# as14120_usb.net
KiCad netlist of a schematic drawn in Altium Designer
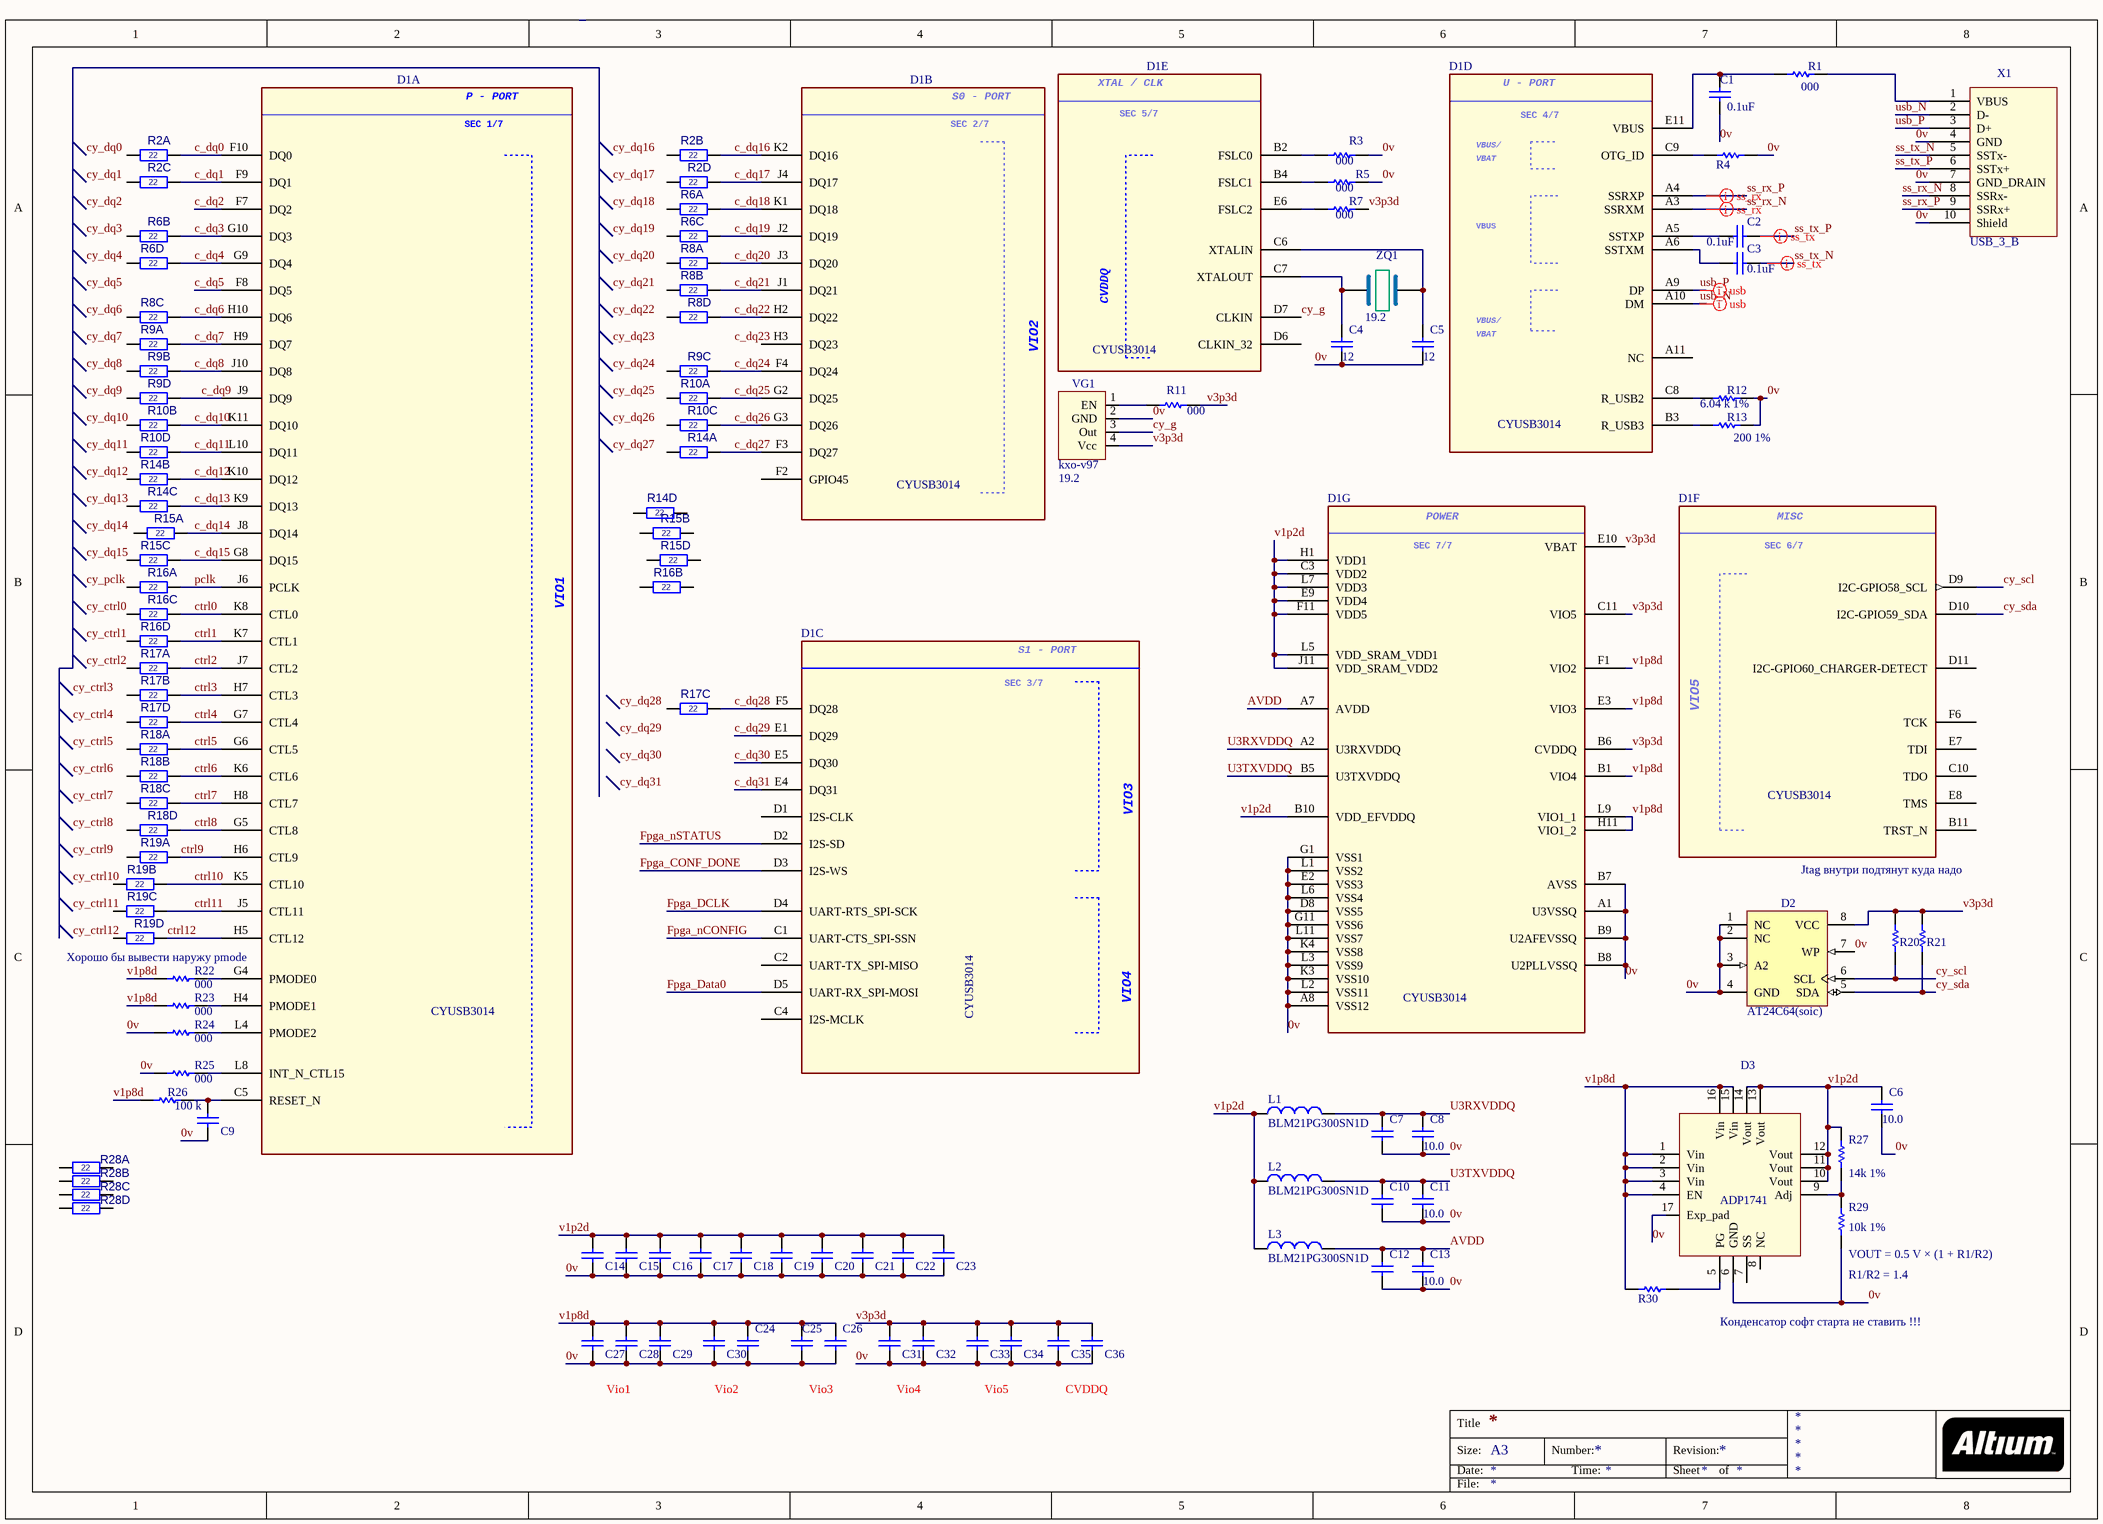
[diagram p0: as14120_usb.SchDoc]

(export (version "E")
  (design (tool "Eeschema 10.0.6"))
  (components
    (comp (ref "C1")
      (value "0.1uF")
      (footprint "CAPC0402(1005)60_M")
      (description "CAP 1uF 10V ±20% 0402 (1005 Metric) Thickness 0.6mm SMD")
      (fields (field (name "TOLERANCE") "±20%") (field (name "Comment") "CAP 1uF 10V 0402(1005)"))
      (libsource (lib "as14120") (part "CAP_0402"))
    )
    (comp (ref "C2")
      (value "0.1uF")
      (footprint "CAPC0402(1005)60_M")
      (description "CAP 1uF 10V ±20% 0402 (1005 Metric) Thickness 0.6mm SMD")
      (fields (field (name "TOLERANCE") "±20%") (field (name "Comment") "CAP 1uF 10V 0402(1005)"))
      (libsource (lib "as14120") (part "CAP_0402"))
    )
    (comp (ref "C3")
      (value "0.1uF")
      (footprint "CAPC0402(1005)60_M")
      (description "CAP 1uF 10V ±20% 0402 (1005 Metric) Thickness 0.6mm SMD")
      (fields (field (name "TOLERANCE") "±20%") (field (name "Comment") "CAP 1uF 10V 0402(1005)"))
      (libsource (lib "as14120") (part "CAP_0402"))
    )
    (comp (ref "C4")
      (value "12")
      (footprint "CAPC0805(2012)100_N")
      (fields (field (name "Comment") "CAP_0805"))
      (libsource (lib "as14120") (part "CAP_0805"))
    )
    (comp (ref "C5")
      (value "12")
      (footprint "CAPC0805(2012)100_N")
      (fields (field (name "Comment") "CAP_0805"))
      (libsource (lib "as14120") (part "CAP_0805"))
    )
    (comp (ref "C6")
      (value "10.0")
      (footprint "CAPC0805(2012)100_N")
      (fields (field (name "Comment") "CAP_0805"))
      (libsource (lib "as14120") (part "CAP_0805"))
    )
    (comp (ref "C7")
      (value "CAP 1uF 10V 0402(1005)")
      (footprint "CAPC0402(1005)60_M")
      (description "CAP 1uF 10V ±20% 0402 (1005 Metric) Thickness 0.6mm SMD")
      (fields (field (name "TOLERANCE") "±20%"))
      (libsource (lib "as14120") (part "CAP_0402"))
    )
    (comp (ref "C8")
      (value "10.0")
      (footprint "CAPC0805(2012)100_N")
      (fields (field (name "Comment") "CAP_0805"))
      (libsource (lib "as14120") (part "CAP_0805"))
    )
    (comp (ref "C9")
      (value "CAP 1uF 10V 0402(1005)")
      (footprint "CAPC0402(1005)60_M")
      (description "CAP 1uF 10V ±20% 0402 (1005 Metric) Thickness 0.6mm SMD")
      (fields (field (name "TOLERANCE") "±20%"))
      (libsource (lib "as14120") (part "CAP_0402"))
    )
    (comp (ref "C10")
      (value "CAP 1uF 10V 0402(1005)")
      (footprint "CAPC0402(1005)60_M")
      (description "CAP 1uF 10V ±20% 0402 (1005 Metric) Thickness 0.6mm SMD")
      (fields (field (name "TOLERANCE") "±20%"))
      (libsource (lib "as14120") (part "CAP_0402"))
    )
    (comp (ref "C11")
      (value "10.0")
      (footprint "CAPC0805(2012)100_N")
      (fields (field (name "Comment") "CAP_0805"))
      (libsource (lib "as14120") (part "CAP_0805"))
    )
    (comp (ref "C12")
      (value "CAP 1uF 10V 0402(1005)")
      (footprint "CAPC0402(1005)60_M")
      (description "CAP 1uF 10V ±20% 0402 (1005 Metric) Thickness 0.6mm SMD")
      (fields (field (name "TOLERANCE") "±20%"))
      (libsource (lib "as14120") (part "CAP_0402"))
    )
    (comp (ref "C13")
      (value "10.0")
      (footprint "CAPC0805(2012)100_N")
      (fields (field (name "Comment") "CAP_0805"))
      (libsource (lib "as14120") (part "CAP_0805"))
    )
    (comp (ref "C14")
      (value "CAP 1uF 10V 0402(1005)")
      (footprint "CAPC0402(1005)60_M")
      (description "CAP 1uF 10V ±20% 0402 (1005 Metric) Thickness 0.6mm SMD")
      (fields (field (name "TOLERANCE") "±20%"))
      (libsource (lib "as14120") (part "CAP_0402"))
    )
    (comp (ref "C15")
      (value "CAP 1uF 10V 0402(1005)")
      (footprint "CAPC0402(1005)60_M")
      (description "CAP 1uF 10V ±20% 0402 (1005 Metric) Thickness 0.6mm SMD")
      (fields (field (name "TOLERANCE") "±20%"))
      (libsource (lib "as14120") (part "CAP_0402"))
    )
    (comp (ref "C16")
      (value "CAP 1uF 10V 0402(1005)")
      (footprint "CAPC0402(1005)60_M")
      (description "CAP 1uF 10V ±20% 0402 (1005 Metric) Thickness 0.6mm SMD")
      (fields (field (name "TOLERANCE") "±20%"))
      (libsource (lib "as14120") (part "CAP_0402"))
    )
    (comp (ref "C17")
      (value "CAP 1uF 10V 0402(1005)")
      (footprint "CAPC0402(1005)60_M")
      (description "CAP 1uF 10V ±20% 0402 (1005 Metric) Thickness 0.6mm SMD")
      (fields (field (name "TOLERANCE") "±20%"))
      (libsource (lib "as14120") (part "CAP_0402"))
    )
    (comp (ref "C18")
      (value "CAP 1uF 10V 0402(1005)")
      (footprint "CAPC0402(1005)60_M")
      (description "CAP 1uF 10V ±20% 0402 (1005 Metric) Thickness 0.6mm SMD")
      (fields (field (name "TOLERANCE") "±20%"))
      (libsource (lib "as14120") (part "CAP_0402"))
    )
    (comp (ref "C19")
      (value "CAP 1uF 10V 0402(1005)")
      (footprint "CAPC0402(1005)60_M")
      (description "CAP 1uF 10V ±20% 0402 (1005 Metric) Thickness 0.6mm SMD")
      (fields (field (name "TOLERANCE") "±20%"))
      (libsource (lib "as14120") (part "CAP_0402"))
    )
    (comp (ref "C20")
      (value "CAP 1uF 10V 0402(1005)")
      (footprint "CAPC0402(1005)60_M")
      (description "CAP 1uF 10V ±20% 0402 (1005 Metric) Thickness 0.6mm SMD")
      (fields (field (name "TOLERANCE") "±20%"))
      (libsource (lib "as14120") (part "CAP_0402"))
    )
    (comp (ref "C21")
      (value "CAP 1uF 10V 0402(1005)")
      (footprint "CAPC0402(1005)60_M")
      (description "CAP 1uF 10V ±20% 0402 (1005 Metric) Thickness 0.6mm SMD")
      (fields (field (name "TOLERANCE") "±20%"))
      (libsource (lib "as14120") (part "CAP_0402"))
    )
    (comp (ref "C22")
      (value "CAP 1uF 10V 0402(1005)")
      (footprint "CAPC0402(1005)60_M")
      (description "CAP 1uF 10V ±20% 0402 (1005 Metric) Thickness 0.6mm SMD")
      (fields (field (name "TOLERANCE") "±20%"))
      (libsource (lib "as14120") (part "CAP_0402"))
    )
    (comp (ref "C23")
      (value "CAP 1uF 10V 0402(1005)")
      (footprint "CAPC0402(1005)60_M")
      (description "CAP 1uF 10V ±20% 0402 (1005 Metric) Thickness 0.6mm SMD")
      (fields (field (name "TOLERANCE") "±20%"))
      (libsource (lib "as14120") (part "CAP_0402"))
    )
    (comp (ref "C24")
      (value "CAP 1uF 10V 0402(1005)")
      (footprint "CAPC0402(1005)60_M")
      (description "CAP 1uF 10V ±20% 0402 (1005 Metric) Thickness 0.6mm SMD")
      (fields (field (name "TOLERANCE") "±20%"))
      (libsource (lib "as14120") (part "CAP_0402"))
    )
    (comp (ref "C25")
      (value "CAP 1uF 10V 0402(1005)")
      (footprint "CAPC0402(1005)60_M")
      (description "CAP 1uF 10V ±20% 0402 (1005 Metric) Thickness 0.6mm SMD")
      (fields (field (name "TOLERANCE") "±20%"))
      (libsource (lib "as14120") (part "CAP_0402"))
    )
    (comp (ref "C26")
      (value "CAP 1uF 10V 0402(1005)")
      (footprint "CAPC0402(1005)60_M")
      (description "CAP 1uF 10V ±20% 0402 (1005 Metric) Thickness 0.6mm SMD")
      (fields (field (name "TOLERANCE") "±20%"))
      (libsource (lib "as14120") (part "CAP_0402"))
    )
    (comp (ref "C27")
      (value "CAP 1uF 10V 0402(1005)")
      (footprint "CAPC0402(1005)60_M")
      (description "CAP 1uF 10V ±20% 0402 (1005 Metric) Thickness 0.6mm SMD")
      (fields (field (name "TOLERANCE") "±20%"))
      (libsource (lib "as14120") (part "CAP_0402"))
    )
    (comp (ref "C28")
      (value "CAP 1uF 10V 0402(1005)")
      (footprint "CAPC0402(1005)60_M")
      (description "CAP 1uF 10V ±20% 0402 (1005 Metric) Thickness 0.6mm SMD")
      (fields (field (name "TOLERANCE") "±20%"))
      (libsource (lib "as14120") (part "CAP_0402"))
    )
    (comp (ref "C29")
      (value "CAP 1uF 10V 0402(1005)")
      (footprint "CAPC0402(1005)60_M")
      (description "CAP 1uF 10V ±20% 0402 (1005 Metric) Thickness 0.6mm SMD")
      (fields (field (name "TOLERANCE") "±20%"))
      (libsource (lib "as14120") (part "CAP_0402"))
    )
    (comp (ref "C30")
      (value "CAP 1uF 10V 0402(1005)")
      (footprint "CAPC0402(1005)60_M")
      (description "CAP 1uF 10V ±20% 0402 (1005 Metric) Thickness 0.6mm SMD")
      (fields (field (name "TOLERANCE") "±20%"))
      (libsource (lib "as14120") (part "CAP_0402"))
    )
    (comp (ref "C31")
      (value "CAP 1uF 10V 0402(1005)")
      (footprint "CAPC0402(1005)60_M")
      (description "CAP 1uF 10V ±20% 0402 (1005 Metric) Thickness 0.6mm SMD")
      (fields (field (name "TOLERANCE") "±20%"))
      (libsource (lib "as14120") (part "CAP_0402"))
    )
    (comp (ref "C32")
      (value "CAP 1uF 10V 0402(1005)")
      (footprint "CAPC0402(1005)60_M")
      (description "CAP 1uF 10V ±20% 0402 (1005 Metric) Thickness 0.6mm SMD")
      (fields (field (name "TOLERANCE") "±20%"))
      (libsource (lib "as14120") (part "CAP_0402"))
    )
    (comp (ref "C33")
      (value "CAP 1uF 10V 0402(1005)")
      (footprint "CAPC0402(1005)60_M")
      (description "CAP 1uF 10V ±20% 0402 (1005 Metric) Thickness 0.6mm SMD")
      (fields (field (name "TOLERANCE") "±20%"))
      (libsource (lib "as14120") (part "CAP_0402"))
    )
    (comp (ref "C34")
      (value "CAP 1uF 10V 0402(1005)")
      (footprint "CAPC0402(1005)60_M")
      (description "CAP 1uF 10V ±20% 0402 (1005 Metric) Thickness 0.6mm SMD")
      (fields (field (name "TOLERANCE") "±20%"))
      (libsource (lib "as14120") (part "CAP_0402"))
    )
    (comp (ref "C35")
      (value "CAP 1uF 10V 0402(1005)")
      (footprint "CAPC0402(1005)60_M")
      (description "CAP 1uF 10V ±20% 0402 (1005 Metric) Thickness 0.6mm SMD")
      (fields (field (name "TOLERANCE") "±20%"))
      (libsource (lib "as14120") (part "CAP_0402"))
    )
    (comp (ref "C36")
      (value "CAP 1uF 10V 0402(1005)")
      (footprint "CAPC0402(1005)60_M")
      (description "CAP 1uF 10V ±20% 0402 (1005 Metric) Thickness 0.6mm SMD")
      (fields (field (name "TOLERANCE") "±20%"))
      (libsource (lib "as14120") (part "CAP_0402"))
    )
    (comp (ref "D1")
      (value "CYUSB3014")
      (footprint "BGA121C80P11X11")
      (libsource (lib "as14120") (part "CYUSB3014-BZXC"))
    )
    (comp (ref "D2")
      (value "AT24C64(soic)")
      (footprint "8S1_N")
      (libsource (lib "Atmel Serial EEPROM") (part "AT24C08BN-SP25-T"))
    )
    (comp (ref "D3") (value "ADP1741") (footprint "CP-16-4_N") (libsource (lib "as14120") (part "ADP1741")))
    (comp (ref "L1")
      (value "BLM21PG300SN1D")
      (footprint "CAPC0805(2012)100_N")
      (libsource (lib "as14120") (part "Ferrite_beat"))
    )
    (comp (ref "L2")
      (value "BLM21PG300SN1D")
      (footprint "CAPC0805(2012)100_N")
      (libsource (lib "as14120") (part "Ferrite_beat"))
    )
    (comp (ref "L3")
      (value "BLM21PG300SN1D")
      (footprint "CAPC0805(2012)100_N")
      (libsource (lib "as14120") (part "Ferrite_beat"))
    )
    (comp (ref "R1")
      (value "000")
      (footprint "RESC0805(2012)_L")
      (description "1K 0.125W 1% 0805 (2012 Metric)  SMD")
      (fields (field (name "TOLERANCE") "1 %") (field (name "POWER") "0.125 W"))
      (libsource (lib "as14120") (part "RES_0805"))
    )
    (comp (ref "R2")
      (value "22")
      (footprint "CAY16")
      (description "RES_CAY16")
      (libsource (lib "") (part "RES_CAY16_1"))
    )
    (comp (ref "R3")
      (value "000")
      (footprint "RESC0603(1608)_L")
      (description "1K 0.1W 5% 0603 (1608 Metric)  SMD")
      (fields (field (name "TOLERANCE") "5 %") (field (name "POWER") "0.1 W"))
      (libsource (lib "as14120") (part "RES_0603"))
    )
    (comp (ref "R4")
      (value "???")
      (footprint "RESC0603(1608)_L")
      (description "1K 0.1W 5% 0603 (1608 Metric)  SMD")
      (fields (field (name "TOLERANCE") "5 %") (field (name "POWER") "0.1 W"))
      (libsource (lib "as14120") (part "RES_0603"))
    )
    (comp (ref "R5")
      (value "000")
      (footprint "RESC0603(1608)_L")
      (description "1K 0.1W 5% 0603 (1608 Metric)  SMD")
      (fields (field (name "TOLERANCE") "5 %") (field (name "POWER") "0.1 W"))
      (libsource (lib "as14120") (part "RES_0603"))
    )
    (comp (ref "R6")
      (value "22")
      (footprint "CAY16")
      (description "RES_CAY16")
      (libsource (lib "") (part "RES_CAY16_7"))
    )
    (comp (ref "R7")
      (value "000")
      (footprint "RESC0603(1608)_L")
      (description "1K 0.1W 5% 0603 (1608 Metric)  SMD")
      (fields (field (name "TOLERANCE") "5 %") (field (name "POWER") "0.1 W"))
      (libsource (lib "as14120") (part "RES_0603"))
    )
    (comp (ref "R8")
      (value "22")
      (footprint "CAY16")
      (description "RES_CAY16")
      (libsource (lib "") (part "RES_CAY16_3"))
    )
    (comp (ref "R9")
      (value "22")
      (footprint "CAY16")
      (description "RES_CAY16")
      (libsource (lib "") (part "RES_CAY16_7"))
    )
    (comp (ref "R10")
      (value "22")
      (footprint "CAY16")
      (description "RES_CAY16")
      (libsource (lib "") (part "RES_CAY16_7"))
    )
    (comp (ref "R11")
      (value "000")
      (footprint "RESC0603(1608)_L")
      (description "1K 0.1W 5% 0603 (1608 Metric)  SMD")
      (fields (field (name "TOLERANCE") "5 %") (field (name "POWER") "0.1 W"))
      (libsource (lib "as14120") (part "RES_0603"))
    )
    (comp (ref "R12")
      (value "6.04 k 1%")
      (footprint "RESC0805(2012)_L")
      (description "1K 0.125W 1% 0805 (2012 Metric)  SMD")
      (fields (field (name "TOLERANCE") "1 %") (field (name "POWER") "0.125 W"))
      (libsource (lib "as14120") (part "RES_0805"))
    )
    (comp (ref "R13")
      (value "200 1%")
      (footprint "RESC0805(2012)_L")
      (description "1K 0.125W 1% 0805 (2012 Metric)  SMD")
      (fields (field (name "TOLERANCE") "1 %") (field (name "POWER") "0.125 W"))
      (libsource (lib "as14120") (part "RES_0805"))
    )
    (comp (ref "R14")
      (value "22")
      (footprint "CAY16")
      (description "RES_CAY16")
      (libsource (lib "alexsb") (part "RES_CAY16"))
    )
    (comp (ref "R15")
      (value "22")
      (footprint "CAY16")
      (description "RES_CAY16")
      (libsource (lib "") (part "RES_CAY16_3"))
    )
    (comp (ref "R16")
      (value "22")
      (footprint "CAY16")
      (description "RES_CAY16")
      (libsource (lib "alexsb") (part "RES_CAY16"))
    )
    (comp (ref "R17")
      (value "22")
      (footprint "CAY16")
      (description "RES_CAY16")
      (libsource (lib "") (part "RES_CAY16_4"))
    )
    (comp (ref "R18")
      (value "22")
      (footprint "CAY16")
      (description "RES_CAY16")
      (libsource (lib "") (part "RES_CAY16_2"))
    )
    (comp (ref "R19")
      (value "22")
      (footprint "CAY16")
      (description "RES_CAY16")
      (libsource (lib "") (part "RES_CAY16_2"))
    )
    (comp (ref "R20")
      (value "1K 5% 0603(1608)")
      (footprint "RESC0603(1608)_L")
      (description "1K 0.1W 5% 0603 (1608 Metric)  SMD")
      (fields (field (name "TOLERANCE") "5 %") (field (name "POWER") "0.1 W"))
      (libsource (lib "as14120") (part "RES_0603"))
    )
    (comp (ref "R21")
      (value "1K 5% 0603(1608)")
      (footprint "RESC0603(1608)_L")
      (description "1K 0.1W 5% 0603 (1608 Metric)  SMD")
      (fields (field (name "TOLERANCE") "5 %") (field (name "POWER") "0.1 W"))
      (libsource (lib "as14120") (part "RES_0603"))
    )
    (comp (ref "R22")
      (value "000")
      (footprint "RESC0603(1608)_L")
      (description "1K 0.1W 5% 0603 (1608 Metric)  SMD")
      (fields (field (name "TOLERANCE") "5 %") (field (name "POWER") "0.1 W"))
      (libsource (lib "as14120") (part "RES_0603"))
    )
    (comp (ref "R23")
      (value "000")
      (footprint "RESC0603(1608)_L")
      (description "1K 0.1W 5% 0603 (1608 Metric)  SMD")
      (fields (field (name "TOLERANCE") "5 %") (field (name "POWER") "0.1 W"))
      (libsource (lib "as14120") (part "RES_0603"))
    )
    (comp (ref "R24")
      (value "000")
      (footprint "RESC0603(1608)_L")
      (description "1K 0.1W 5% 0603 (1608 Metric)  SMD")
      (fields (field (name "TOLERANCE") "5 %") (field (name "POWER") "0.1 W"))
      (libsource (lib "as14120") (part "RES_0603"))
    )
    (comp (ref "R25")
      (value "000")
      (footprint "RESC0603(1608)_L")
      (description "1K 0.1W 5% 0603 (1608 Metric)  SMD")
      (fields (field (name "TOLERANCE") "5 %") (field (name "POWER") "0.1 W"))
      (libsource (lib "as14120") (part "RES_0603"))
    )
    (comp (ref "R26")
      (value "100 k")
      (footprint "RESC0603(1608)_L")
      (description "1K 0.1W 5% 0603 (1608 Metric)  SMD")
      (fields (field (name "TOLERANCE") "5 %") (field (name "POWER") "0.1 W"))
      (libsource (lib "as14120") (part "RES_0603"))
    )
    (comp (ref "R27")
      (value "14k 1%")
      (footprint "RESC0805(2012)_L")
      (description "1K 0.125W 1% 0805 (2012 Metric)  SMD")
      (fields (field (name "TOLERANCE") "1 %") (field (name "POWER") "0.125 W"))
      (libsource (lib "as14120") (part "RES_0805"))
    )
    (comp (ref "R28")
      (value "22")
      (footprint "CAY16")
      (description "RES_CAY16")
      (libsource (lib "alexsb") (part "RES_CAY16"))
    )
    (comp (ref "R29")
      (value "10k 1%")
      (footprint "RESC0805(2012)_L")
      (description "1K 0.125W 1% 0805 (2012 Metric)  SMD")
      (fields (field (name "TOLERANCE") "1 %") (field (name "POWER") "0.125 W"))
      (libsource (lib "as14120") (part "RES_0805"))
    )
    (comp (ref "R30")
      (value "1K 5% 0603(1608)")
      (footprint "RESC0603(1608)_L")
      (description "1K 0.1W 5% 0603 (1608 Metric)  SMD")
      (fields (field (name "TOLERANCE") "5 %") (field (name "POWER") "0.1 W"))
      (libsource (lib "as14120") (part "RES_0603"))
    )
    (comp (ref "VG1")
      (value "kxo-v97")
      (footprint "kxo-v97")
      (fields (field (name "ALTIUM_VALUE") "19.2"))
      (libsource (lib "as14120") (part "kxo-v97"))
    )
    (comp (ref "X1") (value "USB_3_B") (footprint "USB3_B") (libsource (lib "as14120") (part "USB_3_B")))
    (comp (ref "ZQ1")
      (value "19.2")
      (footprint "BCY-W2/E4.7")
      (fields (field (name "Comment") "Resonator"))
      (libsource (lib "as14120") (part "Resonator"))
    )
  )
  (nets
    (net (code "1") (name "/0v") (class "Default")
      (node (ref "C1") (pin "2") (pinfunction "2_2") (pintype "passive"))
      (node (ref "C10") (pin "1") (pinfunction "1_1") (pintype "passive"))
      (node (ref "C11") (pin "1") (pinfunction "1_1") (pintype "passive"))
      (node (ref "C12") (pin "1") (pinfunction "1_1") (pintype "passive"))
      (node (ref "C13") (pin "1") (pinfunction "1_1") (pintype "passive"))
      (node (ref "C14") (pin "1") (pinfunction "1_1") (pintype "passive"))
      (node (ref "C15") (pin "1") (pinfunction "1_1") (pintype "passive"))
      (node (ref "C16") (pin "1") (pinfunction "1_1") (pintype "passive"))
      (node (ref "C17") (pin "1") (pinfunction "1_1") (pintype "passive"))
      (node (ref "C18") (pin "1") (pinfunction "1_1") (pintype "passive"))
      (node (ref "C19") (pin "1") (pinfunction "1_1") (pintype "passive"))
      (node (ref "C20") (pin "1") (pinfunction "1_1") (pintype "passive"))
      (node (ref "C21") (pin "1") (pinfunction "1_1") (pintype "passive"))
      (node (ref "C22") (pin "1") (pinfunction "1_1") (pintype "passive"))
      (node (ref "C23") (pin "1") (pinfunction "1_1") (pintype "passive"))
      (node (ref "C24") (pin "1") (pinfunction "1_1") (pintype "passive"))
      (node (ref "C25") (pin "1") (pinfunction "1_1") (pintype "passive"))
      (node (ref "C26") (pin "1") (pinfunction "1_1") (pintype "passive"))
      (node (ref "C27") (pin "1") (pinfunction "1_1") (pintype "passive"))
      (node (ref "C28") (pin "1") (pinfunction "1_1") (pintype "passive"))
      (node (ref "C29") (pin "1") (pinfunction "1_1") (pintype "passive"))
      (node (ref "C30") (pin "1") (pinfunction "1_1") (pintype "passive"))
      (node (ref "C31") (pin "1") (pinfunction "1_1") (pintype "passive"))
      (node (ref "C32") (pin "1") (pinfunction "1_1") (pintype "passive"))
      (node (ref "C33") (pin "1") (pinfunction "1_1") (pintype "passive"))
      (node (ref "C34") (pin "1") (pinfunction "1_1") (pintype "passive"))
      (node (ref "C35") (pin "1") (pinfunction "1_1") (pintype "passive"))
      (node (ref "C36") (pin "1") (pinfunction "1_1") (pintype "passive"))
      (node (ref "C4") (pin "1") (pinfunction "1_1") (pintype "passive"))
      (node (ref "C5") (pin "1") (pinfunction "1_1") (pintype "passive"))
      (node (ref "C6") (pin "1") (pinfunction "1_1") (pintype "passive"))
      (node (ref "C7") (pin "1") (pinfunction "1_1") (pintype "passive"))
      (node (ref "C8") (pin "1") (pinfunction "1_1") (pintype "passive"))
      (node (ref "C9") (pin "1") (pinfunction "1_1") (pintype "passive"))
      (node (ref "D1") (pin "A1") (pinfunction "U3VSSQ_A1") (pintype "passive"))
      (node (ref "D1") (pin "A8") (pinfunction "VSS12_A8") (pintype "passive"))
      (node (ref "D1") (pin "B7") (pinfunction "AVSS_B7") (pintype "passive"))
      (node (ref "D1") (pin "B8") (pinfunction "U2PLLVSSQ_B8") (pintype "passive"))
      (node (ref "D1") (pin "B9") (pinfunction "U2AFEVSSQ_B9") (pintype "passive"))
      (node (ref "D1") (pin "D8") (pinfunction "VSS5_D8") (pintype "passive"))
      (node (ref "D1") (pin "E2") (pinfunction "VSS3_E2") (pintype "passive"))
      (node (ref "D1") (pin "G1") (pinfunction "VSS1_G1") (pintype "passive"))
      (node (ref "D1") (pin "G11") (pinfunction "VSS6_G11") (pintype "passive"))
      (node (ref "D1") (pin "K3") (pinfunction "VSS10_K3") (pintype "passive"))
      (node (ref "D1") (pin "K4") (pinfunction "VSS8_K4") (pintype "passive"))
      (node (ref "D1") (pin "L1") (pinfunction "VSS2_L1") (pintype "passive"))
      (node (ref "D1") (pin "L11") (pinfunction "VSS7_L11") (pintype "passive"))
      (node (ref "D1") (pin "L2") (pinfunction "VSS11_L2") (pintype "passive"))
      (node (ref "D1") (pin "L3") (pinfunction "VSS9_L3") (pintype "passive"))
      (node (ref "D1") (pin "L6") (pinfunction "VSS4_L6") (pintype "passive"))
      (node (ref "D2") (pin "1") (pinfunction "NC_1") (pintype "passive"))
      (node (ref "D2") (pin "2") (pinfunction "NC_2") (pintype "passive"))
      (node (ref "D2") (pin "3") (pinfunction "A2_3") (pintype "input"))
      (node (ref "D2") (pin "4") (pinfunction "GND_4") (pintype "power_in"))
      (node (ref "D2") (pin "7") (pinfunction "WP_7") (pintype "input"))
      (node (ref "D3") (pin "17") (pinfunction "Exp_pad_17") (pintype "passive"))
      (node (ref "D3") (pin "6") (pinfunction "GND_6") (pintype "passive"))
      (node (ref "R12") (pin "2") (pinfunction "2_2") (pintype "passive"))
      (node (ref "R13") (pin "2") (pinfunction "2_2") (pintype "passive"))
      (node (ref "R24") (pin "2") (pinfunction "2_2") (pintype "passive"))
      (node (ref "R25") (pin "2") (pinfunction "2_2") (pintype "passive"))
      (node (ref "R29") (pin "1") (pinfunction "1_1") (pintype "passive"))
      (node (ref "R3") (pin "1") (pinfunction "1_1") (pintype "passive"))
      (node (ref "R4") (pin "2") (pinfunction "2_2") (pintype "passive"))
      (node (ref "R5") (pin "1") (pinfunction "1_1") (pintype "passive"))
      (node (ref "VG1") (pin "2") (pinfunction "GND_2") (pintype "passive"))
      (node (ref "X1") (pin "10") (pinfunction "Shield_10") (pintype "passive"))
      (node (ref "X1") (pin "4") (pinfunction "GND_4") (pintype "passive"))
      (node (ref "X1") (pin "7") (pinfunction "GND_DRAIN_7") (pintype "passive"))
    )
    (net (code "2") (name "/AVDD") (class "Default")
      (node (ref "C12") (pin "2") (pinfunction "2_2") (pintype "passive"))
      (node (ref "C13") (pin "2") (pinfunction "2_2") (pintype "passive"))
      (node (ref "D1") (pin "A7") (pinfunction "AVDD_A7") (pintype "passive"))
      (node (ref "L3") (pin "2") (pinfunction "2_2") (pintype "passive"))
    )
    (net (code "3") (name "/Fpga_CONF_DONE") (class "Default")
      (node (ref "D1") (pin "D3") (pinfunction "I2S-WS_D3") (pintype "passive"))
    )
    (net (code "4") (name "/Fpga_DCLK") (class "Default")
      (node (ref "D1") (pin "D4") (pinfunction "UART-RTS_SPI-SCK_D4") (pintype "passive"))
    )
    (net (code "5") (name "/Fpga_Data0") (class "Default")
      (node (ref "D1") (pin "D5") (pinfunction "UART-RX_SPI-MOSI_D5") (pintype "passive"))
    )
    (net (code "6") (name "/Fpga_nCONFIG") (class "Default")
      (node (ref "D1") (pin "C1") (pinfunction "UART-CTS_SPI-SSN_C1") (pintype "passive"))
    )
    (net (code "7") (name "/Fpga_nSTATUS") (class "Default")
      (node (ref "D1") (pin "D2") (pinfunction "I2S-SD_D2") (pintype "passive"))
    )
    (net (code "8") (name "/U3RXVDDQ") (class "Default")
      (node (ref "C7") (pin "2") (pinfunction "2_2") (pintype "passive"))
      (node (ref "C8") (pin "2") (pinfunction "2_2") (pintype "passive"))
      (node (ref "D1") (pin "A2") (pinfunction "U3RXVDDQ_A2") (pintype "passive"))
      (node (ref "L1") (pin "2") (pinfunction "2_2") (pintype "passive"))
    )
    (net (code "9") (name "/U3TXVDDQ") (class "Default")
      (node (ref "C10") (pin "2") (pinfunction "2_2") (pintype "passive"))
      (node (ref "C11") (pin "2") (pinfunction "2_2") (pintype "passive"))
      (node (ref "D1") (pin "B5") (pinfunction "U3TXVDDQ_B5") (pintype "passive"))
      (node (ref "L2") (pin "2") (pinfunction "2_2") (pintype "passive"))
    )
    (net (code "10") (name "/c_dq0") (class "Default")
      (node (ref "D1") (pin "F10") (pinfunction "DQ0_F10") (pintype "passive"))
      (node (ref "R2") (pin "8") (pinfunction "2_8") (pintype "passive"))
    )
    (net (code "11") (name "/c_dq1") (class "Default")
      (node (ref "D1") (pin "F9") (pinfunction "DQ1_F9") (pintype "passive"))
      (node (ref "R2") (pin "6") (pinfunction "2_6") (pintype "passive"))
    )
    (net (code "12") (name "/c_dq2") (class "Default")
      (node (ref "D1") (pin "F7") (pinfunction "DQ2_F7") (pintype "passive"))
    )
    (net (code "13") (name "/c_dq3") (class "Default")
      (node (ref "D1") (pin "G10") (pinfunction "DQ3_G10") (pintype "passive"))
      (node (ref "R6") (pin "7") (pinfunction "2_7") (pintype "passive"))
    )
    (net (code "14") (name "/c_dq4") (class "Default")
      (node (ref "D1") (pin "G9") (pinfunction "DQ4_G9") (pintype "passive"))
      (node (ref "R6") (pin "8") (pinfunction "2_8") (pintype "passive"))
    )
    (net (code "15") (name "/c_dq5") (class "Default")
      (node (ref "D1") (pin "F8") (pinfunction "DQ5_F8") (pintype "passive"))
    )
    (net (code "16") (name "/c_dq6") (class "Default")
      (node (ref "D1") (pin "H10") (pinfunction "DQ6_H10") (pintype "passive"))
      (node (ref "R8") (pin "6") (pinfunction "2_6") (pintype "passive"))
    )
    (net (code "17") (name "/c_dq7") (class "Default")
      (node (ref "D1") (pin "H9") (pinfunction "DQ7_H9") (pintype "passive"))
      (node (ref "R9") (pin "8") (pinfunction "2_8") (pintype "passive"))
    )
    (net (code "18") (name "/c_dq8") (class "Default")
      (node (ref "D1") (pin "J10") (pinfunction "DQ8_J10") (pintype "passive"))
      (node (ref "R9") (pin "7") (pinfunction "2_7") (pintype "passive"))
    )
    (net (code "19") (name "/c_dq9") (class "Default")
      (node (ref "D1") (pin "J9") (pinfunction "DQ9_J9") (pintype "passive"))
      (node (ref "R9") (pin "8") (pinfunction "2_8") (pintype "passive"))
    )
    (net (code "20") (name "/c_dq10") (class "Default")
      (node (ref "D1") (pin "K11") (pinfunction "DQ10_K11") (pintype "passive"))
      (node (ref "R10") (pin "7") (pinfunction "2_7") (pintype "passive"))
    )
    (net (code "21") (name "/c_dq11") (class "Default")
      (node (ref "D1") (pin "L10") (pinfunction "DQ11_L10") (pintype "passive"))
      (node (ref "R10") (pin "8") (pinfunction "2_8") (pintype "passive"))
    )
    (net (code "22") (name "/c_dq12") (class "Default")
      (node (ref "D1") (pin "K10") (pinfunction "DQ12_K10") (pintype "passive"))
      (node (ref "R14") (pin "7") (pinfunction "2_7") (pintype "passive"))
    )
    (net (code "23") (name "/c_dq13") (class "Default")
      (node (ref "D1") (pin "K9") (pinfunction "DQ13_K9") (pintype "passive"))
      (node (ref "R14") (pin "6") (pinfunction "2_6") (pintype "passive"))
    )
    (net (code "24") (name "/c_dq14") (class "Default")
      (node (ref "D1") (pin "J8") (pinfunction "DQ14_J8") (pintype "passive"))
      (node (ref "R15") (pin "8") (pinfunction "2_8") (pintype "passive"))
    )
    (net (code "25") (name "/c_dq15") (class "Default")
      (node (ref "D1") (pin "G8") (pinfunction "DQ15_G8") (pintype "passive"))
      (node (ref "R15") (pin "7") (pinfunction "2_7") (pintype "passive"))
    )
    (net (code "26") (name "/c_dq16") (class "Default")
      (node (ref "D1") (pin "K2") (pinfunction "DQ16_K2") (pintype "passive"))
      (node (ref "R2") (pin "7") (pinfunction "2_7") (pintype "passive"))
    )
    (net (code "27") (name "/c_dq17") (class "Default")
      (node (ref "D1") (pin "J4") (pinfunction "DQ17_J4") (pintype "passive"))
      (node (ref "R2") (pin "5") (pinfunction "2_5") (pintype "passive"))
    )
    (net (code "28") (name "/c_dq18") (class "Default")
      (node (ref "D1") (pin "K1") (pinfunction "DQ18_K1") (pintype "passive"))
      (node (ref "R6") (pin "8") (pinfunction "2_8") (pintype "passive"))
    )
    (net (code "29") (name "/c_dq19") (class "Default")
      (node (ref "D1") (pin "J2") (pinfunction "DQ19_J2") (pintype "passive"))
      (node (ref "R6") (pin "6") (pinfunction "2_6") (pintype "passive"))
    )
    (net (code "30") (name "/c_dq20") (class "Default")
      (node (ref "D1") (pin "J3") (pinfunction "DQ20_J3") (pintype "passive"))
      (node (ref "R8") (pin "7") (pinfunction "2_7") (pintype "passive"))
    )
    (net (code "31") (name "/c_dq21") (class "Default")
      (node (ref "D1") (pin "J1") (pinfunction "DQ21_J1") (pintype "passive"))
      (node (ref "R8") (pin "6") (pinfunction "2_6") (pintype "passive"))
    )
    (net (code "32") (name "/c_dq22") (class "Default")
      (node (ref "D1") (pin "H2") (pinfunction "DQ22_H2") (pintype "passive"))
      (node (ref "R8") (pin "5") (pinfunction "2_5") (pintype "passive"))
    )
    (net (code "34") (name "/c_dq24") (class "Default")
      (node (ref "D1") (pin "F4") (pinfunction "DQ24_F4") (pintype "passive"))
      (node (ref "R9") (pin "7") (pinfunction "2_7") (pintype "passive"))
    )
    (net (code "35") (name "/c_dq25") (class "Default")
      (node (ref "D1") (pin "G2") (pinfunction "DQ25_G2") (pintype "passive"))
      (node (ref "R10") (pin "8") (pinfunction "2_8") (pintype "passive"))
    )
    (net (code "36") (name "/c_dq26") (class "Default")
      (node (ref "D1") (pin "G3") (pinfunction "DQ26_G3") (pintype "passive"))
      (node (ref "R10") (pin "6") (pinfunction "2_6") (pintype "passive"))
    )
    (net (code "37") (name "/c_dq27") (class "Default")
      (node (ref "D1") (pin "F3") (pinfunction "DQ27_F3") (pintype "passive"))
      (node (ref "R14") (pin "8") (pinfunction "2_8") (pintype "passive"))
    )
    (net (code "38") (name "/c_dq28") (class "Default")
      (node (ref "D1") (pin "F5") (pinfunction "DQ28_F5") (pintype "passive"))
      (node (ref "R17") (pin "6") (pinfunction "2_6") (pintype "passive"))
    )
    (net (code "39") (name "/c_dq29") (class "Default")
      (node (ref "D1") (pin "E1") (pinfunction "DQ29_E1") (pintype "passive"))
    )
    (net (code "40") (name "/c_dq30") (class "Default")
      (node (ref "D1") (pin "E5") (pinfunction "DQ30_E5") (pintype "passive"))
    )
    (net (code "41") (name "/c_dq31") (class "Default")
      (node (ref "D1") (pin "E4") (pinfunction "DQ31_E4") (pintype "passive"))
    )
    (net (code "42") (name "/ctrl0") (class "Default")
      (node (ref "D1") (pin "K8") (pinfunction "CTL0_K8") (pintype "passive"))
      (node (ref "R16") (pin "6") (pinfunction "2_6") (pintype "passive"))
    )
    (net (code "43") (name "/ctrl1") (class "Default")
      (node (ref "D1") (pin "K7") (pinfunction "CTL1_K7") (pintype "passive"))
      (node (ref "R16") (pin "5") (pinfunction "2_5") (pintype "passive"))
    )
    (net (code "44") (name "/ctrl2") (class "Default")
      (node (ref "D1") (pin "J7") (pinfunction "CTL2_J7") (pintype "passive"))
      (node (ref "R17") (pin "8") (pinfunction "2_8") (pintype "passive"))
    )
    (net (code "45") (name "/ctrl3") (class "Default")
      (node (ref "D1") (pin "H7") (pinfunction "CTL3_H7") (pintype "passive"))
      (node (ref "R17") (pin "7") (pinfunction "2_7") (pintype "passive"))
    )
    (net (code "46") (name "/ctrl4") (class "Default")
      (node (ref "D1") (pin "G7") (pinfunction "CTL4_G7") (pintype "passive"))
      (node (ref "R17") (pin "5") (pinfunction "2_5") (pintype "passive"))
    )
    (net (code "47") (name "/ctrl5") (class "Default")
      (node (ref "D1") (pin "G6") (pinfunction "CTL5_G6") (pintype "passive"))
      (node (ref "R18") (pin "8") (pinfunction "2_8") (pintype "passive"))
    )
    (net (code "48") (name "/ctrl6") (class "Default")
      (node (ref "D1") (pin "K6") (pinfunction "CTL6_K6") (pintype "passive"))
      (node (ref "R18") (pin "7") (pinfunction "2_7") (pintype "passive"))
    )
    (net (code "49") (name "/ctrl7") (class "Default")
      (node (ref "D1") (pin "H8") (pinfunction "CTL7_H8") (pintype "passive"))
      (node (ref "R18") (pin "7") (pinfunction "2_7") (pintype "passive"))
    )
    (net (code "50") (name "/ctrl8") (class "Default")
      (node (ref "D1") (pin "G5") (pinfunction "CTL8_G5") (pintype "passive"))
      (node (ref "R18") (pin "5") (pinfunction "2_5") (pintype "passive"))
    )
    (net (code "51") (name "/ctrl9") (class "Default")
      (node (ref "D1") (pin "H6") (pinfunction "CTL9_H6") (pintype "passive"))
      (node (ref "R19") (pin "5") (pinfunction "2_5") (pintype "passive"))
    )
    (net (code "52") (name "/ctrl10") (class "Default")
      (node (ref "D1") (pin "K5") (pinfunction "CTL10_K5") (pintype "passive"))
      (node (ref "R19") (pin "7") (pinfunction "2_7") (pintype "passive"))
    )
    (net (code "53") (name "/ctrl11") (class "Default")
      (node (ref "D1") (pin "J5") (pinfunction "CTL11_J5") (pintype "passive"))
      (node (ref "R19") (pin "6") (pinfunction "2_6") (pintype "passive"))
    )
    (net (code "54") (name "/ctrl12") (class "Default")
      (node (ref "D1") (pin "H5") (pinfunction "CTL12_H5") (pintype "passive"))
      (node (ref "R19") (pin "5") (pinfunction "2_5") (pintype "passive"))
    )
    (net (code "100") (name "/cy_g") (class "Default")
      (node (ref "D1") (pin "D7") (pinfunction "CLKIN_D7") (pintype "passive"))
      (node (ref "VG1") (pin "3") (pinfunction "Out_3") (pintype "passive"))
    )
    (net (code "102") (name "/cy_scl") (class "Default")
      (node (ref "D1") (pin "D9") (pinfunction "I2C-GPIO58_SCL_D9") (pintype "output"))
      (node (ref "D2") (pin "6") (pinfunction "SCL_6") (pintype "input"))
      (node (ref "R20") (pin "1") (pinfunction "1_1") (pintype "passive"))
    )
    (net (code "103") (name "/cy_sda") (class "Default")
      (node (ref "D1") (pin "D10") (pinfunction "I2C-GPIO59_SDA_D10") (pintype "passive"))
      (node (ref "D2") (pin "5") (pinfunction "SDA_5") (pintype "bidirectional"))
      (node (ref "R21") (pin "1") (pinfunction "1_1") (pintype "passive"))
    )
    (net (code "104") (name "/pclk") (class "Default")
      (node (ref "D1") (pin "J6") (pinfunction "PCLK_J6") (pintype "passive"))
      (node (ref "R16") (pin "8") (pinfunction "2_8") (pintype "passive"))
    )
    (net (code "105") (name "/ss_rx_N") (class "Default")
      (node (ref "D1") (pin "A3") (pinfunction "SSRXM_A3") (pintype "passive"))
      (node (ref "X1") (pin "8") (pinfunction "SSRx-_8") (pintype "passive"))
    )
    (net (code "106") (name "/ss_rx_P") (class "Default")
      (node (ref "D1") (pin "A4") (pinfunction "SSRXP_A4") (pintype "passive"))
      (node (ref "X1") (pin "9") (pinfunction "SSRx+_9") (pintype "passive"))
    )
    (net (code "107") (name "/ss_tx_N") (class "Default")
      (node (ref "C3") (pin "1") (pinfunction "1_1") (pintype "passive"))
      (node (ref "X1") (pin "5") (pinfunction "SSTx-_5") (pintype "passive"))
    )
    (net (code "108") (name "/ss_tx_P") (class "Default")
      (node (ref "C2") (pin "1") (pinfunction "1_1") (pintype "passive"))
      (node (ref "X1") (pin "6") (pinfunction "SSTx+_6") (pintype "passive"))
    )
    (net (code "109") (name "/usb_N") (class "Default")
      (node (ref "D1") (pin "A10") (pinfunction "DM_A10") (pintype "passive"))
      (node (ref "X1") (pin "2") (pinfunction "D-_2") (pintype "passive"))
    )
    (net (code "110") (name "/usb_P") (class "Default")
      (node (ref "D1") (pin "A9") (pinfunction "DP_A9") (pintype "passive"))
      (node (ref "X1") (pin "3") (pinfunction "D+_3") (pintype "passive"))
    )
    (net (code "111") (name "/v1p2d") (class "Default")
      (node (ref "C14") (pin "2") (pinfunction "2_2") (pintype "passive"))
      (node (ref "C15") (pin "2") (pinfunction "2_2") (pintype "passive"))
      (node (ref "C16") (pin "2") (pinfunction "2_2") (pintype "passive"))
      (node (ref "C17") (pin "2") (pinfunction "2_2") (pintype "passive"))
      (node (ref "C18") (pin "2") (pinfunction "2_2") (pintype "passive"))
      (node (ref "C19") (pin "2") (pinfunction "2_2") (pintype "passive"))
      (node (ref "C20") (pin "2") (pinfunction "2_2") (pintype "passive"))
      (node (ref "C21") (pin "2") (pinfunction "2_2") (pintype "passive"))
      (node (ref "C22") (pin "2") (pinfunction "2_2") (pintype "passive"))
      (node (ref "C23") (pin "2") (pinfunction "2_2") (pintype "passive"))
      (node (ref "C6") (pin "2") (pinfunction "2_2") (pintype "passive"))
      (node (ref "D1") (pin "B10") (pinfunction "VDD_EFVDDQ_B10") (pintype "passive"))
      (node (ref "D1") (pin "C3") (pinfunction "VDD2_C3") (pintype "passive"))
      (node (ref "D1") (pin "E9") (pinfunction "VDD4_E9") (pintype "passive"))
      (node (ref "D1") (pin "F11") (pinfunction "VDD5_F11") (pintype "passive"))
      (node (ref "D1") (pin "H1") (pinfunction "VDD1_H1") (pintype "passive"))
      (node (ref "D1") (pin "J11") (pinfunction "VDD_SRAM_VDD2_J11") (pintype "passive"))
      (node (ref "D1") (pin "L5") (pinfunction "VDD_SRAM_VDD1_L5") (pintype "passive"))
      (node (ref "D1") (pin "L7") (pinfunction "VDD3_L7") (pintype "passive"))
      (node (ref "D3") (pin "10") (pinfunction "Vout_10") (pintype "passive"))
      (node (ref "D3") (pin "11") (pinfunction "Vout_11") (pintype "passive"))
      (node (ref "D3") (pin "12") (pinfunction "Vout_12") (pintype "passive"))
      (node (ref "D3") (pin "13") (pinfunction "Vout_13") (pintype "passive"))
      (node (ref "D3") (pin "14") (pinfunction "Vout_14") (pintype "passive"))
      (node (ref "L1") (pin "1") (pinfunction "1_1") (pintype "passive"))
      (node (ref "L2") (pin "1") (pinfunction "1_1") (pintype "passive"))
      (node (ref "L3") (pin "1") (pinfunction "1_1") (pintype "passive"))
      (node (ref "R27") (pin "2") (pinfunction "2_2") (pintype "passive"))
    )
    (net (code "112") (name "/v1p8d") (class "Default")
      (node (ref "C24") (pin "2") (pinfunction "2_2") (pintype "passive"))
      (node (ref "C25") (pin "2") (pinfunction "2_2") (pintype "passive"))
      (node (ref "C26") (pin "2") (pinfunction "2_2") (pintype "passive"))
      (node (ref "C27") (pin "2") (pinfunction "2_2") (pintype "passive"))
      (node (ref "C28") (pin "2") (pinfunction "2_2") (pintype "passive"))
      (node (ref "C29") (pin "2") (pinfunction "2_2") (pintype "passive"))
      (node (ref "C30") (pin "2") (pinfunction "2_2") (pintype "passive"))
      (node (ref "D1") (pin "B1") (pinfunction "VIO4_B1") (pintype "passive"))
      (node (ref "D1") (pin "E3") (pinfunction "VIO3_E3") (pintype "passive"))
      (node (ref "D1") (pin "F1") (pinfunction "VIO2_F1") (pintype "passive"))
      (node (ref "D1") (pin "H11") (pinfunction "VIO1_2_H11") (pintype "passive"))
      (node (ref "D1") (pin "L9") (pinfunction "VIO1_1_L9") (pintype "passive"))
      (node (ref "D3") (pin "1") (pinfunction "Vin_1") (pintype "passive"))
      (node (ref "D3") (pin "15") (pinfunction "Vin_15") (pintype "passive"))
      (node (ref "D3") (pin "16") (pinfunction "Vin_16") (pintype "passive"))
      (node (ref "D3") (pin "2") (pinfunction "Vin_2") (pintype "passive"))
      (node (ref "D3") (pin "3") (pinfunction "Vin_3") (pintype "passive"))
      (node (ref "D3") (pin "4") (pinfunction "EN_4") (pintype "passive"))
      (node (ref "R22") (pin "2") (pinfunction "2_2") (pintype "passive"))
      (node (ref "R23") (pin "2") (pinfunction "2_2") (pintype "passive"))
      (node (ref "R26") (pin "2") (pinfunction "2_2") (pintype "passive"))
      (node (ref "R30") (pin "2") (pinfunction "2_2") (pintype "passive"))
    )
    (net (code "113") (name "/v3p3d") (class "Default")
      (node (ref "C31") (pin "2") (pinfunction "2_2") (pintype "passive"))
      (node (ref "C32") (pin "2") (pinfunction "2_2") (pintype "passive"))
      (node (ref "C33") (pin "2") (pinfunction "2_2") (pintype "passive"))
      (node (ref "C34") (pin "2") (pinfunction "2_2") (pintype "passive"))
      (node (ref "C35") (pin "2") (pinfunction "2_2") (pintype "passive"))
      (node (ref "C36") (pin "2") (pinfunction "2_2") (pintype "passive"))
      (node (ref "D1") (pin "B6") (pinfunction "CVDDQ_B6") (pintype "passive"))
      (node (ref "D1") (pin "C11") (pinfunction "VIO5_C11") (pintype "passive"))
      (node (ref "D1") (pin "E10") (pinfunction "VBAT_E10") (pintype "passive"))
      (node (ref "D2") (pin "8") (pinfunction "VCC_8") (pintype "power_in"))
      (node (ref "R11") (pin "1") (pinfunction "1_1") (pintype "passive"))
      (node (ref "R20") (pin "2") (pinfunction "2_2") (pintype "passive"))
      (node (ref "R21") (pin "2") (pinfunction "2_2") (pintype "passive"))
      (node (ref "R7") (pin "1") (pinfunction "1_1") (pintype "passive"))
      (node (ref "VG1") (pin "4") (pinfunction "Vcc_4") (pintype "passive"))
    )
    (net (code "114") (name "Net-(D1A-INT_N_CTL15)") (class "Default")
      (node (ref "D1") (pin "L8") (pinfunction "INT_N_CTL15_L8") (pintype "passive"))
      (node (ref "R25") (pin "1") (pinfunction "1_1") (pintype "passive"))
    )
    (net (code "115") (name "Net-(D1A-PMODE0)") (class "Default")
      (node (ref "D1") (pin "G4") (pinfunction "PMODE0_G4") (pintype "passive"))
      (node (ref "R22") (pin "1") (pinfunction "1_1") (pintype "passive"))
    )
    (net (code "116") (name "Net-(D1A-PMODE1)") (class "Default")
      (node (ref "D1") (pin "H4") (pinfunction "PMODE1_H4") (pintype "passive"))
      (node (ref "R23") (pin "1") (pinfunction "1_1") (pintype "passive"))
    )
    (net (code "117") (name "Net-(D1A-PMODE2)") (class "Default")
      (node (ref "D1") (pin "L4") (pinfunction "PMODE2_L4") (pintype "passive"))
      (node (ref "R24") (pin "1") (pinfunction "1_1") (pintype "passive"))
    )
    (net (code "118") (name "Net-(D1A-RESET_N)") (class "Default")
      (node (ref "C9") (pin "2") (pinfunction "2_2") (pintype "passive"))
      (node (ref "D1") (pin "C5") (pinfunction "RESET_N_C5") (pintype "passive"))
      (node (ref "R26") (pin "1") (pinfunction "1_1") (pintype "passive"))
    )
    (net (code "119") (name "Net-(D1D-OTG_ID)") (class "Default")
      (node (ref "D1") (pin "C9") (pinfunction "OTG_ID_C9") (pintype "passive"))
      (node (ref "R4") (pin "1") (pinfunction "1_1") (pintype "passive"))
    )
    (net (code "120") (name "Net-(D1D-R_USB2)") (class "Default")
      (node (ref "D1") (pin "C8") (pinfunction "R_USB2_C8") (pintype "passive"))
      (node (ref "R12") (pin "1") (pinfunction "1_1") (pintype "passive"))
    )
    (net (code "121") (name "Net-(D1D-R_USB3)") (class "Default")
      (node (ref "D1") (pin "B3") (pinfunction "R_USB3_B3") (pintype "passive"))
      (node (ref "R13") (pin "1") (pinfunction "1_1") (pintype "passive"))
    )
    (net (code "122") (name "Net-(D1D-SSTXM)") (class "Default")
      (node (ref "C3") (pin "2") (pinfunction "2_2") (pintype "passive"))
      (node (ref "D1") (pin "A6") (pinfunction "SSTXM_A6") (pintype "passive"))
    )
    (net (code "123") (name "Net-(D1D-SSTXP)") (class "Default")
      (node (ref "C2") (pin "2") (pinfunction "2_2") (pintype "passive"))
      (node (ref "D1") (pin "A5") (pinfunction "SSTXP_A5") (pintype "passive"))
    )
    (net (code "124") (name "Net-(D1D-VBUS)") (class "Default")
      (node (ref "C1") (pin "1") (pinfunction "1_1") (pintype "passive"))
      (node (ref "D1") (pin "E11") (pinfunction "VBUS_E11") (pintype "passive"))
      (node (ref "R1") (pin "1") (pinfunction "1_1") (pintype "passive"))
    )
    (net (code "125") (name "Net-(D1E-FSLC0)") (class "Default")
      (node (ref "D1") (pin "B2") (pinfunction "FSLC0_B2") (pintype "passive"))
      (node (ref "R3") (pin "2") (pinfunction "2_2") (pintype "passive"))
    )
    (net (code "126") (name "Net-(D1E-FSLC1)") (class "Default")
      (node (ref "D1") (pin "B4") (pinfunction "FSLC1_B4") (pintype "passive"))
      (node (ref "R5") (pin "2") (pinfunction "2_2") (pintype "passive"))
    )
    (net (code "127") (name "Net-(D1E-FSLC2)") (class "Default")
      (node (ref "D1") (pin "E6") (pinfunction "FSLC2_E6") (pintype "passive"))
      (node (ref "R7") (pin "2") (pinfunction "2_2") (pintype "passive"))
    )
    (net (code "128") (name "Net-(D1E-XTALIN)") (class "Default")
      (node (ref "C5") (pin "2") (pinfunction "2_2") (pintype "passive"))
      (node (ref "D1") (pin "C6") (pinfunction "XTALIN_C6") (pintype "passive"))
      (node (ref "ZQ1") (pin "2") (pinfunction "2_2") (pintype "passive"))
    )
    (net (code "129") (name "Net-(D1E-XTALOUT)") (class "Default")
      (node (ref "C4") (pin "2") (pinfunction "2_2") (pintype "passive"))
      (node (ref "D1") (pin "C7") (pinfunction "XTALOUT_C7") (pintype "passive"))
      (node (ref "ZQ1") (pin "1") (pinfunction "1_1") (pintype "passive"))
    )
    (net (code "130") (name "Net-(D3-Adj)") (class "Default")
      (node (ref "D3") (pin "9") (pinfunction "Adj_9") (pintype "passive"))
      (node (ref "R27") (pin "1") (pinfunction "1_1") (pintype "passive"))
      (node (ref "R29") (pin "2") (pinfunction "2_2") (pintype "passive"))
    )
    (net (code "131") (name "Net-(D3-PG)") (class "Default")
      (node (ref "D3") (pin "5") (pinfunction "PG_5") (pintype "passive"))
      (node (ref "R30") (pin "1") (pinfunction "1_1") (pintype "passive"))
    )
    (net (code "132") (name "Net-(VG1-EN)") (class "Default")
      (node (ref "R11") (pin "2") (pinfunction "2_2") (pintype "passive"))
      (node (ref "VG1") (pin "1") (pinfunction "EN_1") (pintype "passive"))
    )
    (net (code "133") (name "Net-(X1-VBUS)") (class "Default")
      (node (ref "R1") (pin "2") (pinfunction "2_2") (pintype "passive"))
      (node (ref "X1") (pin "1") (pinfunction "VBUS_1") (pintype "passive"))
    )
    (net (code "134") (name "unconnected-(D1B-DQ23-PadH3)") (class "Default")
      (node (ref "D1") (pin "H3") (pinfunction "DQ23_H3") (pintype "passive"))
    )
    (net (code "135") (name "unconnected-(D1B-GPIO45-PadF2)") (class "Default")
      (node (ref "D1") (pin "F2") (pinfunction "GPIO45_F2") (pintype "passive"))
    )
    (net (code "136") (name "unconnected-(D1C-I2S-CLK-PadD1)") (class "Default")
      (node (ref "D1") (pin "D1") (pinfunction "I2S-CLK_D1") (pintype "passive"))
    )
    (net (code "137") (name "unconnected-(D1C-I2S-MCLK-PadC4)") (class "Default")
      (node (ref "D1") (pin "C4") (pinfunction "I2S-MCLK_C4") (pintype "passive"))
    )
    (net (code "138") (name "unconnected-(D1C-UART-TX_SPI-MISO-PadC2)") (class "Default")
      (node (ref "D1") (pin "C2") (pinfunction "UART-TX_SPI-MISO_C2") (pintype "passive"))
    )
    (net (code "139") (name "unconnected-(D1D-NC-PadA11)") (class "Default")
      (node (ref "D1") (pin "A11") (pinfunction "NC_A11") (pintype "passive"))
    )
    (net (code "140") (name "unconnected-(D1E-CLKIN_32-PadD6)") (class "Default")
      (node (ref "D1") (pin "D6") (pinfunction "CLKIN_32_D6") (pintype "passive"))
    )
    (net (code "141") (name "unconnected-(D1F-I2C-GPIO60_CHARGER-DETECT-PadD11)") (class "Default")
      (node (ref "D1") (pin "D11") (pinfunction "I2C-GPIO60_CHARGER-DETECT_D11") (pintype "passive"))
    )
    (net (code "142") (name "unconnected-(D1F-TCK-PadF6)") (class "Default")
      (node (ref "D1") (pin "F6") (pinfunction "TCK_F6") (pintype "passive"))
    )
    (net (code "143") (name "unconnected-(D1F-TDI-PadE7)") (class "Default")
      (node (ref "D1") (pin "E7") (pinfunction "TDI_E7") (pintype "passive"))
    )
    (net (code "144") (name "unconnected-(D1F-TDO-PadC10)") (class "Default")
      (node (ref "D1") (pin "C10") (pinfunction "TDO_C10") (pintype "passive"))
    )
    (net (code "145") (name "unconnected-(D1F-TMS-PadE8)") (class "Default")
      (node (ref "D1") (pin "E8") (pinfunction "TMS_E8") (pintype "passive"))
    )
    (net (code "146") (name "unconnected-(D1F-TRST_N-PadB11)") (class "Default")
      (node (ref "D1") (pin "B11") (pinfunction "TRST_N_B11") (pintype "passive"))
    )
    (net (code "147") (name "unconnected-(D3-NC-Pad8)") (class "Default")
      (node (ref "D3") (pin "8") (pinfunction "NC_8") (pintype "passive"))
    )
    (net (code "148") (name "unconnected-(D3-SS-Pad7)") (class "Default")
      (node (ref "D3") (pin "7") (pinfunction "SS_7") (pintype "passive"))
    )
    (net (code "149") (name "unconnected-(R2-Pad1)") (class "Default")
      (node (ref "R2") (pin "1") (pinfunction "1_1") (pintype "passive"))
    )
    (net (code "150") (name "unconnected-(R2B-1-Pad2)") (class "Default")
      (node (ref "R2") (pin "2") (pinfunction "1_2") (pintype "passive"))
    )
    (net (code "151") (name "unconnected-(R2C-1-Pad3)") (class "Default")
      (node (ref "R2") (pin "3") (pinfunction "1_3") (pintype "passive"))
    )
    (net (code "152") (name "unconnected-(R2D-1-Pad4)") (class "Default")
      (node (ref "R2") (pin "4") (pinfunction "1_4") (pintype "passive"))
    )
    (net (code "153") (name "unconnected-(R6-Pad1)") (class "Default")
      (node (ref "R6") (pin "1") (pinfunction "1_1") (pintype "passive"))
    )
    (net (code "154") (name "unconnected-(R6B-1-Pad2)") (class "Default")
      (node (ref "R6") (pin "2") (pinfunction "1_2") (pintype "passive"))
    )
    (net (code "155") (name "unconnected-(R6C-1-Pad3)") (class "Default")
      (node (ref "R6") (pin "3") (pinfunction "1_3") (pintype "passive"))
    )
    (net (code "156") (name "unconnected-(R6D-1-Pad4)") (class "Default")
      (node (ref "R6") (pin "4") (pinfunction "1_4") (pintype "passive"))
    )
    (net (code "157") (name "unconnected-(R8-Pad1)") (class "Default")
      (node (ref "R8") (pin "1") (pinfunction "1_1") (pintype "passive"))
    )
    (net (code "158") (name "unconnected-(R8B-1-Pad2)") (class "Default")
      (node (ref "R8") (pin "2") (pinfunction "1_2") (pintype "passive"))
    )
    (net (code "159") (name "unconnected-(R8C-1-Pad3)") (class "Default")
      (node (ref "R8") (pin "3") (pinfunction "1_3") (pintype "passive"))
    )
    (net (code "160") (name "unconnected-(R8D-1-Pad4)") (class "Default")
      (node (ref "R8") (pin "4") (pinfunction "1_4") (pintype "passive"))
    )
    (net (code "161") (name "unconnected-(R9-Pad1)") (class "Default")
      (node (ref "R9") (pin "1") (pinfunction "1_1") (pintype "passive"))
    )
    (net (code "162") (name "unconnected-(R9B-1-Pad2)") (class "Default")
      (node (ref "R9") (pin "2") (pinfunction "1_2") (pintype "passive"))
    )
    (net (code "163") (name "unconnected-(R9C-1-Pad3)") (class "Default")
      (node (ref "R9") (pin "3") (pinfunction "1_3") (pintype "passive"))
    )
    (net (code "164") (name "unconnected-(R9D-1-Pad4)") (class "Default")
      (node (ref "R9") (pin "4") (pinfunction "1_4") (pintype "passive"))
    )
    (net (code "165") (name "unconnected-(R10-Pad1)") (class "Default")
      (node (ref "R10") (pin "1") (pinfunction "1_1") (pintype "passive"))
    )
    (net (code "166") (name "unconnected-(R10B-1-Pad2)") (class "Default")
      (node (ref "R10") (pin "2") (pinfunction "1_2") (pintype "passive"))
    )
    (net (code "167") (name "unconnected-(R10C-1-Pad3)") (class "Default")
      (node (ref "R10") (pin "3") (pinfunction "1_3") (pintype "passive"))
    )
    (net (code "168") (name "unconnected-(R10D-1-Pad4)") (class "Default")
      (node (ref "R10") (pin "4") (pinfunction "1_4") (pintype "passive"))
    )
    (net (code "169") (name "unconnected-(R14-Pad1)") (class "Default")
      (node (ref "R14") (pin "1") (pinfunction "1_1") (pintype "passive"))
    )
    (net (code "170") (name "unconnected-(R14B-1-Pad2)") (class "Default")
      (node (ref "R14") (pin "2") (pinfunction "1_2") (pintype "passive"))
    )
    (net (code "171") (name "unconnected-(R14C-1-Pad3)") (class "Default")
      (node (ref "R14") (pin "3") (pinfunction "1_3") (pintype "passive"))
    )
    (net (code "172") (name "unconnected-(R14D-1-Pad4)") (class "Default")
      (node (ref "R14") (pin "4") (pinfunction "1_4") (pintype "passive"))
    )
    (net (code "173") (name "unconnected-(R14D-2-Pad5)") (class "Default")
      (node (ref "R14") (pin "5") (pinfunction "2_5") (pintype "passive"))
    )
    (net (code "174") (name "unconnected-(R15-Pad1)") (class "Default")
      (node (ref "R15") (pin "1") (pinfunction "1_1") (pintype "passive"))
    )
    (net (code "175") (name "unconnected-(R15B-1-Pad2)") (class "Default")
      (node (ref "R15") (pin "2") (pinfunction "1_2") (pintype "passive"))
    )
    (net (code "176") (name "unconnected-(R15B-2-Pad7)") (class "Default")
      (node (ref "R15") (pin "7") (pinfunction "2_7") (pintype "passive"))
    )
    (net (code "177") (name "unconnected-(R15C-1-Pad3)") (class "Default")
      (node (ref "R15") (pin "3") (pinfunction "1_3") (pintype "passive"))
    )
    (net (code "178") (name "unconnected-(R15D-1-Pad4)") (class "Default")
      (node (ref "R15") (pin "4") (pinfunction "1_4") (pintype "passive"))
    )
    (net (code "179") (name "unconnected-(R15D-2-Pad5)") (class "Default")
      (node (ref "R15") (pin "5") (pinfunction "2_5") (pintype "passive"))
    )
    (net (code "180") (name "unconnected-(R16-Pad1)") (class "Default")
      (node (ref "R16") (pin "1") (pinfunction "1_1") (pintype "passive"))
    )
    (net (code "181") (name "unconnected-(R16B-1-Pad2)") (class "Default")
      (node (ref "R16") (pin "2") (pinfunction "1_2") (pintype "passive"))
    )
    (net (code "182") (name "unconnected-(R16B-2-Pad7)") (class "Default")
      (node (ref "R16") (pin "7") (pinfunction "2_7") (pintype "passive"))
    )
    (net (code "183") (name "unconnected-(R16C-1-Pad3)") (class "Default")
      (node (ref "R16") (pin "3") (pinfunction "1_3") (pintype "passive"))
    )
    (net (code "184") (name "unconnected-(R16D-1-Pad4)") (class "Default")
      (node (ref "R16") (pin "4") (pinfunction "1_4") (pintype "passive"))
    )
    (net (code "185") (name "unconnected-(R17-Pad1)") (class "Default")
      (node (ref "R17") (pin "1") (pinfunction "1_1") (pintype "passive"))
    )
    (net (code "186") (name "unconnected-(R17B-1-Pad2)") (class "Default")
      (node (ref "R17") (pin "2") (pinfunction "1_2") (pintype "passive"))
    )
    (net (code "187") (name "unconnected-(R17C-1-Pad3)") (class "Default")
      (node (ref "R17") (pin "3") (pinfunction "1_3") (pintype "passive"))
    )
    (net (code "188") (name "unconnected-(R17D-1-Pad4)") (class "Default")
      (node (ref "R17") (pin "4") (pinfunction "1_4") (pintype "passive"))
    )
    (net (code "189") (name "unconnected-(R18-Pad1)") (class "Default")
      (node (ref "R18") (pin "1") (pinfunction "1_1") (pintype "passive"))
    )
    (net (code "190") (name "unconnected-(R18B-1-Pad2)") (class "Default")
      (node (ref "R18") (pin "2") (pinfunction "1_2") (pintype "passive"))
    )
    (net (code "191") (name "unconnected-(R18C-1-Pad3)") (class "Default")
      (node (ref "R18") (pin "3") (pinfunction "1_3") (pintype "passive"))
    )
    (net (code "192") (name "unconnected-(R18D-1-Pad4)") (class "Default")
      (node (ref "R18") (pin "4") (pinfunction "1_4") (pintype "passive"))
    )
    (net (code "193") (name "unconnected-(R19-Pad1)") (class "Default")
      (node (ref "R19") (pin "1") (pinfunction "1_1") (pintype "passive"))
    )
    (net (code "194") (name "unconnected-(R19B-1-Pad2)") (class "Default")
      (node (ref "R19") (pin "2") (pinfunction "1_2") (pintype "passive"))
    )
    (net (code "195") (name "unconnected-(R19C-1-Pad3)") (class "Default")
      (node (ref "R19") (pin "3") (pinfunction "1_3") (pintype "passive"))
    )
    (net (code "196") (name "unconnected-(R19D-1-Pad4)") (class "Default")
      (node (ref "R19") (pin "4") (pinfunction "1_4") (pintype "passive"))
    )
    (net (code "197") (name "unconnected-(R28-Pad1)") (class "Default")
      (node (ref "R28") (pin "1") (pinfunction "1_1") (pintype "passive"))
    )
    (net (code "198") (name "unconnected-(R28A-2-Pad8)") (class "Default")
      (node (ref "R28") (pin "8") (pinfunction "2_8") (pintype "passive"))
    )
    (net (code "199") (name "unconnected-(R28B-1-Pad2)") (class "Default")
      (node (ref "R28") (pin "2") (pinfunction "1_2") (pintype "passive"))
    )
    (net (code "200") (name "unconnected-(R28B-2-Pad7)") (class "Default")
      (node (ref "R28") (pin "7") (pinfunction "2_7") (pintype "passive"))
    )
    (net (code "201") (name "unconnected-(R28C-1-Pad3)") (class "Default")
      (node (ref "R28") (pin "3") (pinfunction "1_3") (pintype "passive"))
    )
    (net (code "202") (name "unconnected-(R28C-2-Pad6)") (class "Default")
      (node (ref "R28") (pin "6") (pinfunction "2_6") (pintype "passive"))
    )
    (net (code "203") (name "unconnected-(R28D-1-Pad4)") (class "Default")
      (node (ref "R28") (pin "4") (pinfunction "1_4") (pintype "passive"))
    )
    (net (code "204") (name "unconnected-(R28D-2-Pad5)") (class "Default")
      (node (ref "R28") (pin "5") (pinfunction "2_5") (pintype "passive"))
    )
  )
)
